# Gilbert_Cell_Mixer.net
KiCad netlist of a schematic drawn in Altium Designer
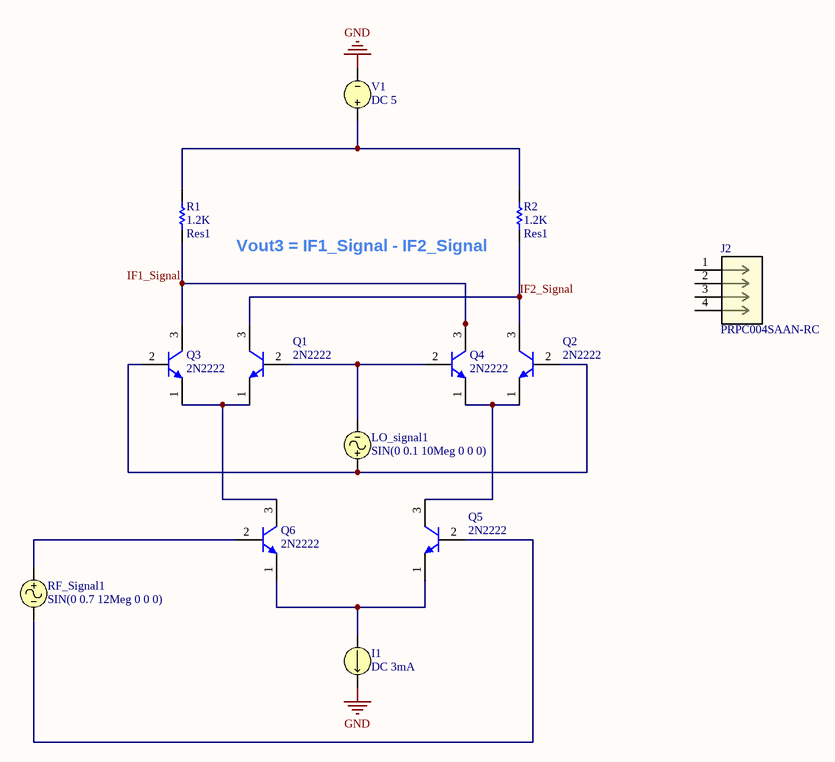
[diagram p0: Gilbert Cell Mixer.SchDoc]

(export (version "E")
  (design (tool "Eeschema 10.0.6"))
  (components
    (comp (ref "I1")
      (value "DC 3mA")
      (description "Current Source")
      (fields (field (name "PUBLISHER") "Altium Limited"))
      (libsource (lib "Simulation Generic Components") (part "ISRC"))
    )
    (comp (ref "J2")
      (value "PRPC004SAAN-RC")
      (footprint "CONN4_PRPC004_SUL")
      (description "No Description Available")
      (libsource (lib "PRPC004SAAN-RC") (part "PRPC004SAAN-RC"))
    )
    (comp (ref "LO_signal1")
      (value "SIN(0 0.1 10Meg 0 0 0)")
      (description "Sinusoidal Voltage Source")
      (fields (field (name "PUBLISHER") "Altium Limited"))
      (libsource (lib "Simulation Generic Components") (part "VSIN"))
    )
    (comp (ref "Q1")
      (value "2N2222")
      (footprint "MLTC-TO-18-3")
      (description "Low Power Bipolar NPN Transistor, 30 V, -65 to 200 degC, 3-Pin TO-18, RoHS, Bulk")
      (fields (field (name "MANUFACTURER") "Multicomp"))
      (libsource (lib "Altium Content Vault") (part "BJT-NPN-EBC-3"))
    )
    (comp (ref "Q2")
      (value "2N2222")
      (footprint "MLTC-TO-18-3")
      (description "Low Power Bipolar NPN Transistor, 30 V, -65 to 200 degC, 3-Pin TO-18, RoHS, Bulk")
      (fields (field (name "MANUFACTURER") "Multicomp"))
      (libsource (lib "Altium Content Vault") (part "BJT-NPN-EBC-3"))
    )
    (comp (ref "Q3")
      (value "2N2222")
      (footprint "MLTC-TO-18-3")
      (description "Low Power Bipolar NPN Transistor, 30 V, -65 to 200 degC, 3-Pin TO-18, RoHS, Bulk")
      (fields (field (name "MANUFACTURER") "Multicomp"))
      (libsource (lib "Altium Content Vault") (part "BJT-NPN-EBC-3"))
    )
    (comp (ref "Q4")
      (value "2N2222")
      (footprint "MLTC-TO-18-3")
      (description "Low Power Bipolar NPN Transistor, 30 V, -65 to 200 degC, 3-Pin TO-18, RoHS, Bulk")
      (fields (field (name "MANUFACTURER") "Multicomp"))
      (libsource (lib "Altium Content Vault") (part "BJT-NPN-EBC-3"))
    )
    (comp (ref "Q5")
      (value "2N2222")
      (footprint "MLTC-TO-18-3")
      (description "Low Power Bipolar NPN Transistor, 30 V, -65 to 200 degC, 3-Pin TO-18, RoHS, Bulk")
      (fields (field (name "MANUFACTURER") "Multicomp"))
      (libsource (lib "Altium Content Vault") (part "BJT-NPN-EBC-3"))
    )
    (comp (ref "Q6")
      (value "2N2222")
      (footprint "MLTC-TO-18-3")
      (description "Low Power Bipolar NPN Transistor, 30 V, -65 to 200 degC, 3-Pin TO-18, RoHS, Bulk")
      (fields (field (name "MANUFACTURER") "Multicomp"))
      (libsource (lib "Altium Content Vault") (part "BJT-NPN-EBC-3"))
    )
    (comp (ref "R1")
      (value "Res1")
      (footprint "AXIAL-0.1-RES")
      (description "Resistor")
      (fields
        (field (name "ALTIUM_VALUE") "1.2K")
        (field (name "MANUFACTURER PART NUMBER") "CFR-25JB-52-1K2")
        (field (name "TOLERANCE") "0.05")
        (field (name "PUBLISHER") "Altium Limited")
      )
      (libsource (lib "ECE295-Resistors-TH") (part "RES 1.2K OHM 5% 1/4W AXIAL"))
    )
    (comp (ref "R2")
      (value "Res1")
      (footprint "AXIAL-0.1-RES")
      (description "Resistor")
      (fields
        (field (name "ALTIUM_VALUE") "1.2K")
        (field (name "MANUFACTURER PART NUMBER") "CFR-25JB-52-1K2")
        (field (name "TOLERANCE") "0.05")
        (field (name "PUBLISHER") "Altium Limited")
      )
      (libsource (lib "ECE295-Resistors-TH") (part "RES 1.2K OHM 5% 1/4W AXIAL"))
    )
    (comp (ref "RF_Signal1")
      (value "SIN(0 0.7 12Meg 0 0 0)")
      (description "Sinusoidal Voltage Source")
      (fields (field (name "PUBLISHER") "Altium Limited"))
      (libsource (lib "Simulation Generic Components") (part "VSIN"))
    )
    (comp (ref "V1")
      (value "DC 5")
      (description "Voltage Source")
      (fields (field (name "PUBLISHER") "Altium Limited"))
      (libsource (lib "Simulation Generic Components") (part "VSRC"))
    )
  )
  (nets
    (net (code "1") (name "/IF1_Signal") (class "Default")
      (node (ref "Q3") (pin "3") (pinfunction "C_3") (pintype "passive"))
      (node (ref "Q4") (pin "3") (pinfunction "C_3") (pintype "passive"))
      (node (ref "R1") (pin "1") (pinfunction "1_1") (pintype "passive"))
    )
    (net (code "2") (name "/IF2_Signal") (class "Default")
      (node (ref "Q1") (pin "3") (pinfunction "C_3") (pintype "passive"))
      (node (ref "Q2") (pin "3") (pinfunction "C_3") (pintype "passive"))
      (node (ref "R2") (pin "1") (pinfunction "1_1") (pintype "passive"))
    )
    (net (code "3") (name "GND") (class "Default")
      (node (ref "I1") (pin "2") (pinfunction "2_2") (pintype "passive"))
      (node (ref "V1") (pin "2") (pinfunction "2_2") (pintype "passive"))
    )
    (net (code "4") (name "Net-(Q1-B)") (class "Default")
      (node (ref "LO_signal1") (pin "2") (pinfunction "2_2") (pintype "passive"))
      (node (ref "Q1") (pin "2") (pinfunction "B_2") (pintype "passive"))
      (node (ref "Q4") (pin "2") (pinfunction "B_2") (pintype "passive"))
    )
    (net (code "5") (name "Net-(Q1-E)") (class "Default")
      (node (ref "Q1") (pin "1") (pinfunction "E_1") (pintype "passive"))
      (node (ref "Q3") (pin "1") (pinfunction "E_1") (pintype "passive"))
      (node (ref "Q6") (pin "3") (pinfunction "C_3") (pintype "passive"))
    )
    (net (code "6") (name "Net-(Q2-B)") (class "Default")
      (node (ref "LO_signal1") (pin "1") (pinfunction "1_1") (pintype "passive"))
      (node (ref "Q2") (pin "2") (pinfunction "B_2") (pintype "passive"))
      (node (ref "Q3") (pin "2") (pinfunction "B_2") (pintype "passive"))
    )
    (net (code "7") (name "Net-(Q2-E)") (class "Default")
      (node (ref "Q2") (pin "1") (pinfunction "E_1") (pintype "passive"))
      (node (ref "Q4") (pin "1") (pinfunction "E_1") (pintype "passive"))
      (node (ref "Q5") (pin "3") (pinfunction "C_3") (pintype "passive"))
    )
    (net (code "8") (name "Net-(Q5-B)") (class "Default")
      (node (ref "Q5") (pin "2") (pinfunction "B_2") (pintype "passive"))
      (node (ref "RF_Signal1") (pin "2") (pinfunction "2_2") (pintype "passive"))
    )
    (net (code "9") (name "Net-(Q5-E)") (class "Default")
      (node (ref "I1") (pin "1") (pinfunction "1_1") (pintype "passive"))
      (node (ref "Q5") (pin "1") (pinfunction "E_1") (pintype "passive"))
      (node (ref "Q6") (pin "1") (pinfunction "E_1") (pintype "passive"))
    )
    (net (code "10") (name "Net-(Q6-B)") (class "Default")
      (node (ref "Q6") (pin "2") (pinfunction "B_2") (pintype "passive"))
      (node (ref "RF_Signal1") (pin "1") (pinfunction "1_1") (pintype "passive"))
    )
    (net (code "11") (name "Net-(R1-Pad2)") (class "Default")
      (node (ref "R1") (pin "2") (pinfunction "2_2") (pintype "passive"))
      (node (ref "R2") (pin "2") (pinfunction "2_2") (pintype "passive"))
      (node (ref "V1") (pin "1") (pinfunction "1_1") (pintype "passive"))
    )
    (net (code "12") (name "unconnected-(J2-Pad1)") (class "Default")
      (node (ref "J2") (pin "1") (pinfunction "1_1") (pintype "passive"))
    )
    (net (code "13") (name "unconnected-(J2-Pad2)") (class "Default")
      (node (ref "J2") (pin "2") (pinfunction "2_2") (pintype "passive"))
    )
    (net (code "14") (name "unconnected-(J2-Pad3)") (class "Default")
      (node (ref "J2") (pin "3") (pinfunction "3_3") (pintype "passive"))
    )
    (net (code "15") (name "unconnected-(J2-Pad4)") (class "Default")
      (node (ref "J2") (pin "4") (pinfunction "4_4") (pintype "passive"))
    )
  )
)
